# Schematic.net
KiCad netlist of a schematic drawn in Altium Designer
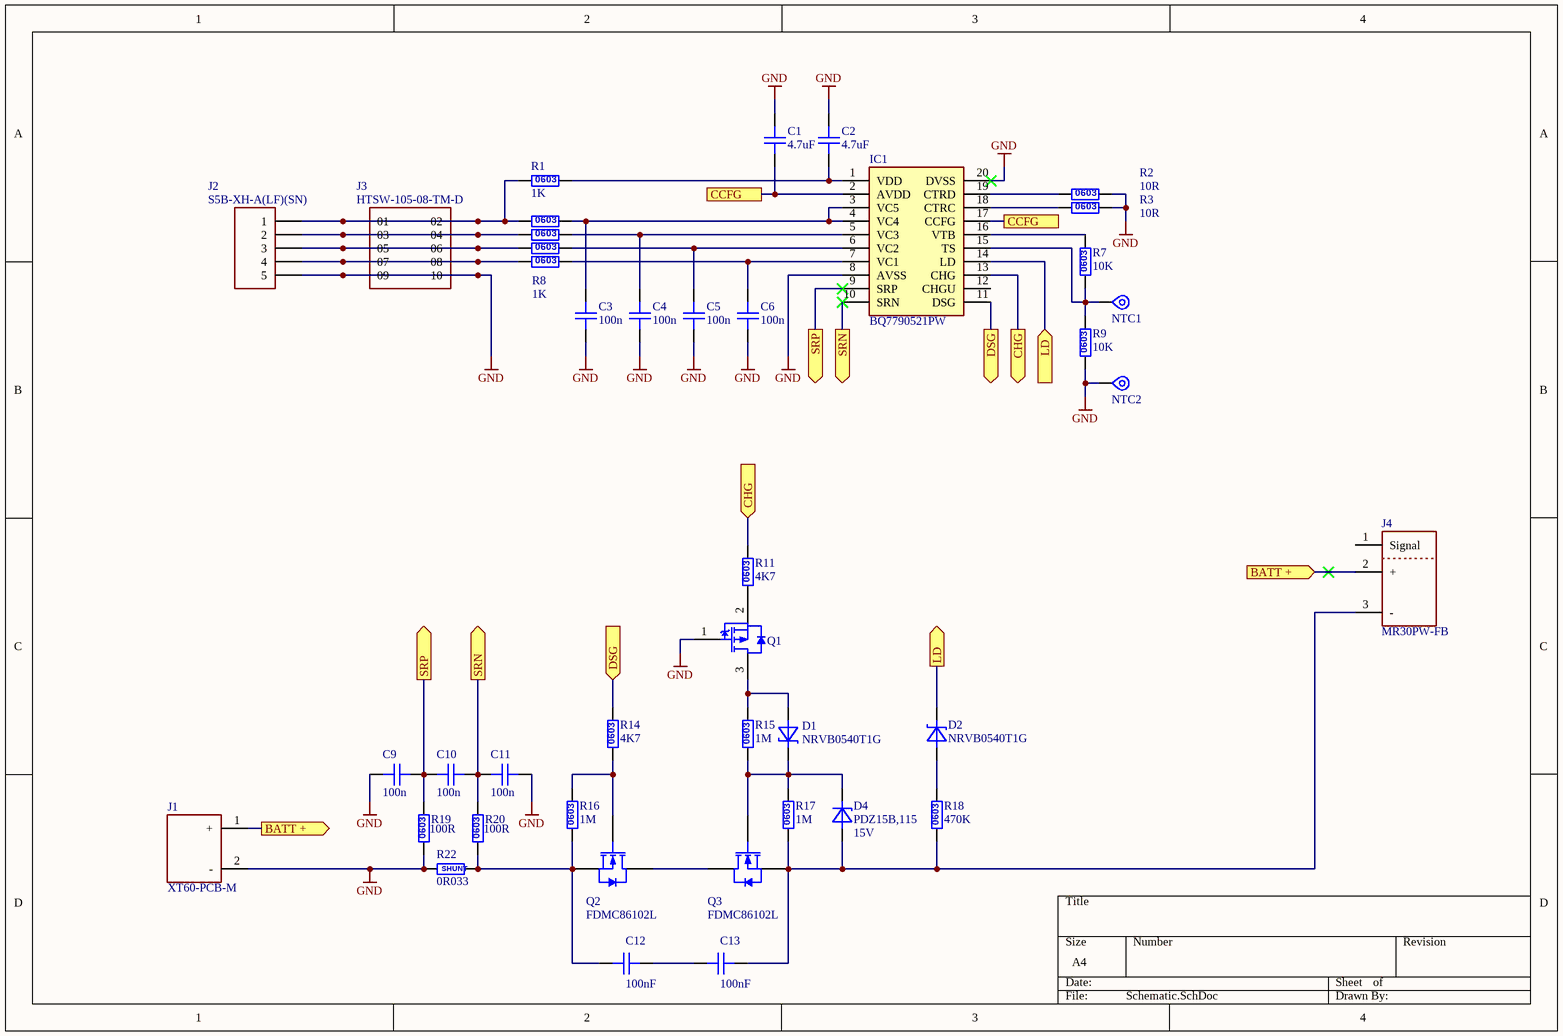
[diagram p0: Schematic.SchDoc]

(export (version "E")
  (design (tool "Eeschema 10.0.6"))
  (components
    (comp (ref "C1")
      (value "4.7uF")
      (footprint "C3216_Commercial")
      (description "Capacitor X7S")
      (fields (field (name "Comment") "GRM31CC72A475ME11L"))
      (libsource (lib "CapRes") (part "CC_1206_X7S_475"))
    )
    (comp (ref "C2")
      (value "4.7uF")
      (footprint "C3216_Commercial")
      (description "Capacitor X7S")
      (fields (field (name "Comment") "GRM31CC72A475ME11L"))
      (libsource (lib "CapRes") (part "CC_1206_X7S_475"))
    )
    (comp (ref "C3")
      (value "100n")
      (footprint "C0603")
      (description "Ceramic Capacitor X7R 50V")
      (fields (field (name "PART NUMBER") "100n/50V X7R C0603") (field (name "Comment") "06035C104K4Z2A"))
      (libsource (lib "CapRes") (part "CC_0603_X7R_104"))
    )
    (comp (ref "C4")
      (value "100n")
      (footprint "C0603")
      (description "Ceramic Capacitor X7R 50V")
      (fields (field (name "PART NUMBER") "100n/50V X7R C0603") (field (name "Comment") "06035C104K4Z2A"))
      (libsource (lib "CapRes") (part "CC_0603_X7R_104"))
    )
    (comp (ref "C5")
      (value "100n")
      (footprint "C0603")
      (description "Ceramic Capacitor X7R 50V")
      (fields (field (name "PART NUMBER") "100n/50V X7R C0603") (field (name "Comment") "06035C104K4Z2A"))
      (libsource (lib "CapRes") (part "CC_0603_X7R_104"))
    )
    (comp (ref "C6")
      (value "100n")
      (footprint "C0603")
      (description "Ceramic Capacitor X7R 50V")
      (fields (field (name "PART NUMBER") "100n/50V X7R C0603") (field (name "Comment") "06035C104K4Z2A"))
      (libsource (lib "CapRes") (part "CC_0603_X7R_104"))
    )
    (comp (ref "C9")
      (value "100n")
      (footprint "C0603")
      (description "Ceramic Capacitor X7R 50V")
      (fields (field (name "PART NUMBER") "100n/50V X7R C0603") (field (name "Comment") "06035C104K4Z2A"))
      (libsource (lib "CapRes") (part "CC_0603_X7R_104"))
    )
    (comp (ref "C10")
      (value "100n")
      (footprint "C0603")
      (description "Ceramic Capacitor X7R 50V")
      (fields (field (name "PART NUMBER") "100n/50V X7R C0603") (field (name "Comment") "06035C104K4Z2A"))
      (libsource (lib "CapRes") (part "CC_0603_X7R_104"))
    )
    (comp (ref "C11")
      (value "100n")
      (footprint "C0603")
      (description "Ceramic Capacitor X7R 50V")
      (fields (field (name "PART NUMBER") "100n/50V X7R C0603") (field (name "Comment") "06035C104K4Z2A"))
      (libsource (lib "CapRes") (part "CC_0603_X7R_104"))
    )
    (comp (ref "C12")
      (value "100nF")
      (footprint "C3216_Commercial")
      (description "Capacitor NP0")
      (fields (field (name "Comment") "GRT31C5C2A104JA12L"))
      (libsource (lib "CapRes") (part "CC_1206_NP0_104"))
    )
    (comp (ref "C13")
      (value "100nF")
      (footprint "C3216_Commercial")
      (description "Capacitor NP0")
      (fields (field (name "Comment") "GRT31C5C2A104JA12L"))
      (libsource (lib "CapRes") (part "CC_1206_NP0_104"))
    )
    (comp (ref "D1")
      (value "NRVB0540T1G")
      (footprint "SOD323")
      (description "Schottky Diode 40V, 500mA")
      (libsource (lib "Semi") (part "NRVB0540T1G"))
    )
    (comp (ref "D2")
      (value "NRVB0540T1G")
      (footprint "SOD323")
      (description "Schottky Diode 40V, 500mA")
      (libsource (lib "Semi") (part "NRVB0540T1G"))
    )
    (comp (ref "D4")
      (value "PDZ15B,115")
      (footprint "SOD323")
      (description "Zener Diode 15V, 400mW")
      (fields (field (name "ALTIUM_VALUE") "15V"))
      (libsource (lib "Semi") (part "PDZ15B,115"))
    )
    (comp (ref "IC1")
      (value "BQ7790521PW")
      (footprint "SOP65P640X120-20N")
      (description "3- to 5-series Li-Ion stackable battery protector")
      (fields (field (name "MOUSER PART NUMBER") "595-BQ7790521PW"))
      (libsource (lib "Semi") (part "BQ7790521PW"))
    )
    (comp (ref "J1")
      (value "XT60-PCB-M")
      (footprint "XT60-PCB-M")
      (description "XT60 Connector")
      (fields (field (name "MANUFACTURER_PART_NUMBER") "XT30PB"))
      (libsource (lib "CapRes") (part "XT60-PCB-M"))
    )
    (comp (ref "J2")
      (value "S5B-XH-A(LF)(SN)")
      (footprint "JST_S5B-XH-A(LF)(SN)")
      (description "Connector Header Through Hole, Right Angle 5 position 0.098 _2.50mm_")
      (fields (field (name "MF") "JST Sales") (field (name "MP") "S5B-XH-A_LF__SN_"))
      (libsource (lib "CapRes") (part "S5B-XH-A(LF)(SN)"))
    )
    (comp (ref "J3")
      (value "HTSW-105-08-TM-D")
      (footprint "SAMTEC_HTSW-105-08-TM-D")
      (fields (field (name "MP") "HTSW10508TMD") (field (name "MF") "Samtec"))
      (libsource (lib "CapRes") (part "HTSW-105-08-TM-D"))
    )
    (comp (ref "J4")
      (value "MR30PW-FB")
      (footprint "MR30PW-FB")
      (description "Connector")
      (libsource (lib "CapRes") (part "MR30PW-FB"))
    )
    (comp (ref "NTC1")
      (value "TP")
      (footprint "Pad0.8mm MPoint big")
      (description "Test Point")
      (libsource (lib "CapRes") (part "TP_PCB"))
    )
    (comp (ref "NTC2")
      (value "TP")
      (footprint "Pad0.8mm MPoint big")
      (description "Test Point")
      (libsource (lib "CapRes") (part "TP_PCB"))
    )
    (comp (ref "Q1")
      (value "FDV304P")
      (footprint "FAIR-SOT23-3_V")
      (fields (field (name "MANUFACTURER") "ON Semiconductor / Fairchild"))
      (libsource (lib "Semi") (part "FDV304P"))
    )
    (comp (ref "Q2")
      (value "FDMC86102L")
      (footprint "PowerPak1212_LFPAK33")
      (description "N-MOS 100V, 18A, 23mOhm")
      (fields (field (name "MANUFACTURER") "ON Semiconductor / Fairchild"))
      (libsource (lib "Semi") (part "FDMC86102L"))
    )
    (comp (ref "Q3")
      (value "FDMC86102L")
      (footprint "PowerPak1212_LFPAK33")
      (description "N-MOS 100V, 18A, 23mOhm")
      (fields (field (name "MANUFACTURER") "ON Semiconductor / Fairchild"))
      (libsource (lib "Semi") (part "FDMC86102L"))
    )
    (comp (ref "R1")
      (value "1K")
      (footprint "R0603")
      (description "Resistor 1%, 0.1W, 75V")
      (fields (field (name "Comment") "ERJ-3EKF1002V"))
      (libsource (lib "CapRes") (part "CR_0603_102"))
    )
    (comp (ref "R2")
      (value "10R")
      (footprint "R0603")
      (description "Resistor 1%, 0.1W, 75V")
      (fields (field (name "Comment") "CR0603-FX-10R0ELF"))
      (libsource (lib "CapRes") (part "CR_0603_100"))
    )
    (comp (ref "R3")
      (value "10R")
      (footprint "R0603")
      (description "Resistor 1%, 0.1W, 75V")
      (fields (field (name "Comment") "CR0603-FX-10R0ELF"))
      (libsource (lib "CapRes") (part "CR_0603_100"))
    )
    (comp (ref "R4")
      (value "ERJ-3EKF1002V")
      (footprint "R0603")
      (description "Resistor 1%, 0.1W, 75V")
      (libsource (lib "CapRes") (part "CR_0603_102"))
    )
    (comp (ref "R5")
      (value "ERJ-3EKF1002V")
      (footprint "R0603")
      (description "Resistor 1%, 0.1W, 75V")
      (libsource (lib "CapRes") (part "CR_0603_102"))
    )
    (comp (ref "R6")
      (value "ERJ-3EKF1002V")
      (footprint "R0603")
      (description "Resistor 1%, 0.1W, 75V")
      (libsource (lib "CapRes") (part "CR_0603_102"))
    )
    (comp (ref "R7")
      (value "10K")
      (footprint "R0603")
      (description "Resistor 1%, 0.1W, 75V")
      (fields (field (name "Comment") "CRGP0603F10K"))
      (libsource (lib "CapRes") (part "CR_0603_103"))
    )
    (comp (ref "R8")
      (value "1K")
      (footprint "R0603")
      (description "Resistor 1%, 0.1W, 75V")
      (fields (field (name "Comment") "ERJ-3EKF1002V"))
      (libsource (lib "CapRes") (part "CR_0603_102"))
    )
    (comp (ref "R9")
      (value "10K")
      (footprint "R0603")
      (description "Resistor 1%, 0.1W, 75V")
      (fields (field (name "Comment") "CRGP0603F10K"))
      (libsource (lib "CapRes") (part "CR_0603_103"))
    )
    (comp (ref "R11")
      (value "4K7")
      (footprint "R0603")
      (description "Resistor 1%, 0.1W, 75V")
      (fields (field (name "Comment") "RC0603FR-074K7L"))
      (libsource (lib "CapRes") (part "CR_0603_472"))
    )
    (comp (ref "R14")
      (value "4K7")
      (footprint "R0603")
      (description "Resistor 1%, 0.1W, 75V")
      (fields (field (name "Comment") "RC0603FR-074K7L"))
      (libsource (lib "CapRes") (part "CR_0603_472"))
    )
    (comp (ref "R15")
      (value "1M")
      (footprint "R0603")
      (description "Resistor 1%, 0.1W, 75V")
      (fields (field (name "PART NUMBER") "1M0 R0603") (field (name "Comment") "RC0603JR-071ML"))
      (libsource (lib "CapRes") (part "CR_0603_105"))
    )
    (comp (ref "R16")
      (value "1M")
      (footprint "R0603")
      (description "Resistor 1%, 0.1W, 75V")
      (fields (field (name "PART NUMBER") "1M0 R0603") (field (name "Comment") "RC0603JR-071ML"))
      (libsource (lib "CapRes") (part "CR_0603_105"))
    )
    (comp (ref "R17")
      (value "1M")
      (footprint "R0603")
      (description "Resistor 1%, 0.1W, 75V")
      (fields (field (name "PART NUMBER") "1M0 R0603") (field (name "Comment") "RC0603JR-071ML"))
      (libsource (lib "CapRes") (part "CR_0603_105"))
    )
    (comp (ref "R18")
      (value "470K")
      (footprint "R0603")
      (description "Resistor 1%, 0.1W, 75V")
      (fields (field (name "Comment") "CRGCQ0603F470K"))
      (libsource (lib "CapRes") (part "CR_0603_474"))
    )
    (comp (ref "R19")
      (value "100R")
      (footprint "R0603")
      (description "Resistor 1%, 0.1W, 75V")
      (fields (field (name "Comment") "RC0603FR-07100RL"))
      (libsource (lib "CapRes") (part "CR_0603_101"))
    )
    (comp (ref "R20")
      (value "100R")
      (footprint "R0603")
      (description "Resistor 1%, 0.1W, 75V")
      (fields (field (name "Comment") "RC0603FR-07100RL"))
      (libsource (lib "CapRes") (part "CR_0603_101"))
    )
    (comp (ref "R22")
      (value "0R033")
      (footprint "Shunt_2512")
      (description "Current Sense Resistor 1%, 3W, AEC-Q200")
      (fields (field (name "Comment") "GMR100HTBFMR033"))
      (libsource (lib "CapRes") (part "SHUNT_2512_0R033"))
    )
  )
  (nets
    (net (code "1") (name "/BATT +") (class "Default")
      (node (ref "J1") (pin "1") (pinfunction "+_1") (pintype "passive"))
      (node (ref "J4") (pin "2") (pinfunction "+_2") (pintype "passive"))
    )
    (net (code "2") (name "/CCFG") (class "Default")
      (node (ref "C1") (pin "1") (pinfunction "1_1") (pintype "passive"))
      (node (ref "IC1") (pin "17") (pinfunction "CCFG_17") (pintype "passive"))
      (node (ref "IC1") (pin "2") (pinfunction "AVDD_2") (pintype "passive"))
    )
    (net (code "3") (name "/CHG") (class "Default")
      (node (ref "IC1") (pin "13") (pinfunction "CHG_13") (pintype "passive"))
      (node (ref "R11") (pin "1") (pinfunction "1_1") (pintype "passive"))
    )
    (net (code "4") (name "/DSG") (class "Default")
      (node (ref "IC1") (pin "11") (pinfunction "DSG_11") (pintype "passive"))
      (node (ref "R14") (pin "1") (pinfunction "1_1") (pintype "passive"))
    )
    (net (code "5") (name "/LD") (class "Default")
      (node (ref "D2") (pin "2") (pinfunction "C_2") (pintype "passive"))
      (node (ref "IC1") (pin "14") (pinfunction "LD_14") (pintype "passive"))
    )
    (net (code "6") (name "/SRN") (class "Default")
      (node (ref "C10") (pin "2") (pinfunction "2_2") (pintype "passive"))
      (node (ref "C11") (pin "1") (pinfunction "1_1") (pintype "passive"))
      (node (ref "IC1") (pin "10") (pinfunction "SRN_10") (pintype "passive"))
      (node (ref "R20") (pin "1") (pinfunction "1_1") (pintype "passive"))
    )
    (net (code "7") (name "/SRP") (class "Default")
      (node (ref "C10") (pin "1") (pinfunction "1_1") (pintype "passive"))
      (node (ref "C9") (pin "2") (pinfunction "2_2") (pintype "passive"))
      (node (ref "IC1") (pin "9") (pinfunction "SRP_9") (pintype "passive"))
      (node (ref "R19") (pin "1") (pinfunction "1_1") (pintype "passive"))
    )
    (net (code "8") (name "GND") (class "Default")
      (node (ref "C1") (pin "2") (pinfunction "2_2") (pintype "passive"))
      (node (ref "C11") (pin "2") (pinfunction "2_2") (pintype "passive"))
      (node (ref "C2") (pin "2") (pinfunction "2_2") (pintype "passive"))
      (node (ref "C3") (pin "1") (pinfunction "1_1") (pintype "passive"))
      (node (ref "C4") (pin "1") (pinfunction "1_1") (pintype "passive"))
      (node (ref "C5") (pin "1") (pinfunction "1_1") (pintype "passive"))
      (node (ref "C6") (pin "1") (pinfunction "1_1") (pintype "passive"))
      (node (ref "C9") (pin "1") (pinfunction "1_1") (pintype "passive"))
      (node (ref "IC1") (pin "20") (pinfunction "DVSS_20") (pintype "passive"))
      (node (ref "IC1") (pin "8") (pinfunction "AVSS_8") (pintype "passive"))
      (node (ref "J1") (pin "2") (pinfunction "-_2") (pintype "passive"))
      (node (ref "J2") (pin "5") (pinfunction "5_5") (pintype "passive"))
      (node (ref "J3") (pin "09") (pinfunction "09_09") (pintype "passive"))
      (node (ref "J3") (pin "10") (pinfunction "10_10") (pintype "passive"))
      (node (ref "NTC2") (pin "1") (pinfunction "1_1") (pintype "passive"))
      (node (ref "Q1") (pin "1") (pinfunction "G_1") (pintype "passive"))
      (node (ref "R19") (pin "2") (pinfunction "2_2") (pintype "passive"))
      (node (ref "R2") (pin "1") (pinfunction "1_1") (pintype "passive"))
      (node (ref "R22") (pin "1") (pinfunction "1_1") (pintype "passive"))
      (node (ref "R3") (pin "1") (pinfunction "1_1") (pintype "passive"))
      (node (ref "R9") (pin "2") (pinfunction "2_2") (pintype "passive"))
    )
    (net (code "9") (name "Net-(C12-Pad1)") (class "Default")
      (node (ref "C12") (pin "1") (pinfunction "1_1") (pintype "passive"))
      (node (ref "Q2") (pin "1") (pinfunction "SOURCE_1") (pintype "passive"))
      (node (ref "Q2") (pin "2") (pinfunction "SOURCE_2") (pintype "passive"))
      (node (ref "Q2") (pin "3") (pinfunction "SOURCE_3") (pintype "passive"))
      (node (ref "R16") (pin "2") (pinfunction "2_2") (pintype "passive"))
      (node (ref "R20") (pin "2") (pinfunction "2_2") (pintype "passive"))
      (node (ref "R22") (pin "2") (pinfunction "2_2") (pintype "passive"))
    )
    (net (code "10") (name "Net-(C12-Pad2)") (class "Default")
      (node (ref "C12") (pin "2") (pinfunction "2_2") (pintype "passive"))
      (node (ref "C13") (pin "1") (pinfunction "1_1") (pintype "passive"))
    )
    (net (code "11") (name "Net-(D1-A)") (class "Default")
      (node (ref "D1") (pin "1") (pinfunction "A_1") (pintype "passive"))
      (node (ref "Q1") (pin "3") (pinfunction "D_3") (pintype "passive"))
      (node (ref "R15") (pin "1") (pinfunction "1_1") (pintype "passive"))
    )
    (net (code "12") (name "Net-(D1-C)") (class "Default")
      (node (ref "D1") (pin "2") (pinfunction "C_2") (pintype "passive"))
      (node (ref "D4") (pin "2") (pinfunction "C_2") (pintype "passive"))
      (node (ref "Q3") (pin "4") (pinfunction "GATE_4") (pintype "passive"))
      (node (ref "R15") (pin "2") (pinfunction "2_2") (pintype "passive"))
      (node (ref "R17") (pin "1") (pinfunction "1_1") (pintype "passive"))
    )
    (net (code "13") (name "Net-(D2-A)") (class "Default")
      (node (ref "D2") (pin "1") (pinfunction "A_1") (pintype "passive"))
      (node (ref "R18") (pin "1") (pinfunction "1_1") (pintype "passive"))
    )
    (net (code "14") (name "Net-(D4-A)") (class "Default")
      (node (ref "C13") (pin "2") (pinfunction "2_2") (pintype "passive"))
      (node (ref "D4") (pin "1") (pinfunction "A_1") (pintype "passive"))
      (node (ref "J4") (pin "3") (pinfunction "-_3") (pintype "passive"))
      (node (ref "Q3") (pin "1") (pinfunction "SOURCE_1") (pintype "passive"))
      (node (ref "Q3") (pin "2") (pinfunction "SOURCE_2") (pintype "passive"))
      (node (ref "Q3") (pin "3") (pinfunction "SOURCE_3") (pintype "passive"))
      (node (ref "R17") (pin "2") (pinfunction "2_2") (pintype "passive"))
      (node (ref "R18") (pin "2") (pinfunction "2_2") (pintype "passive"))
    )
    (net (code "15") (name "Net-(IC1-CTRC)") (class "Default")
      (node (ref "IC1") (pin "18") (pinfunction "CTRC_18") (pintype "passive"))
      (node (ref "R3") (pin "2") (pinfunction "2_2") (pintype "passive"))
    )
    (net (code "16") (name "Net-(IC1-CTRD)") (class "Default")
      (node (ref "IC1") (pin "19") (pinfunction "CTRD_19") (pintype "passive"))
      (node (ref "R2") (pin "2") (pinfunction "2_2") (pintype "passive"))
    )
    (net (code "17") (name "Net-(IC1-TS)") (class "Default")
      (node (ref "IC1") (pin "15") (pinfunction "TS_15") (pintype "passive"))
      (node (ref "NTC1") (pin "1") (pinfunction "1_1") (pintype "passive"))
      (node (ref "R7") (pin "2") (pinfunction "2_2") (pintype "passive"))
      (node (ref "R9") (pin "1") (pinfunction "1_1") (pintype "passive"))
    )
    (net (code "18") (name "Net-(IC1-VC1)") (class "Default")
      (node (ref "C6") (pin "2") (pinfunction "2_2") (pintype "passive"))
      (node (ref "IC1") (pin "7") (pinfunction "VC1_7") (pintype "passive"))
      (node (ref "R6") (pin "1") (pinfunction "1_1") (pintype "passive"))
    )
    (net (code "19") (name "Net-(IC1-VC2)") (class "Default")
      (node (ref "C5") (pin "2") (pinfunction "2_2") (pintype "passive"))
      (node (ref "IC1") (pin "6") (pinfunction "VC2_6") (pintype "passive"))
      (node (ref "R5") (pin "1") (pinfunction "1_1") (pintype "passive"))
    )
    (net (code "20") (name "Net-(IC1-VC3)") (class "Default")
      (node (ref "C4") (pin "2") (pinfunction "2_2") (pintype "passive"))
      (node (ref "IC1") (pin "5") (pinfunction "VC3_5") (pintype "passive"))
      (node (ref "R4") (pin "1") (pinfunction "1_1") (pintype "passive"))
    )
    (net (code "21") (name "Net-(IC1-VC4)") (class "Default")
      (node (ref "C3") (pin "2") (pinfunction "2_2") (pintype "passive"))
      (node (ref "IC1") (pin "3") (pinfunction "VC5_3") (pintype "passive"))
      (node (ref "IC1") (pin "4") (pinfunction "VC4_4") (pintype "passive"))
      (node (ref "R8") (pin "1") (pinfunction "1_1") (pintype "passive"))
    )
    (net (code "22") (name "Net-(IC1-VDD)") (class "Default")
      (node (ref "C2") (pin "1") (pinfunction "1_1") (pintype "passive"))
      (node (ref "IC1") (pin "1") (pinfunction "VDD_1") (pintype "passive"))
      (node (ref "R1") (pin "1") (pinfunction "1_1") (pintype "passive"))
    )
    (net (code "23") (name "Net-(IC1-VTB)") (class "Default")
      (node (ref "IC1") (pin "16") (pinfunction "VTB_16") (pintype "passive"))
      (node (ref "R7") (pin "1") (pinfunction "1_1") (pintype "passive"))
    )
    (net (code "24") (name "Net-(J2-Pad1)") (class "Default")
      (node (ref "J2") (pin "1") (pinfunction "1_1") (pintype "passive"))
      (node (ref "J3") (pin "01") (pinfunction "01_01") (pintype "passive"))
      (node (ref "J3") (pin "02") (pinfunction "02_02") (pintype "passive"))
      (node (ref "R1") (pin "2") (pinfunction "2_2") (pintype "passive"))
      (node (ref "R8") (pin "2") (pinfunction "2_2") (pintype "passive"))
    )
    (net (code "25") (name "Net-(J2-Pad2)") (class "Default")
      (node (ref "J2") (pin "2") (pinfunction "2_2") (pintype "passive"))
      (node (ref "J3") (pin "03") (pinfunction "03_03") (pintype "passive"))
      (node (ref "J3") (pin "04") (pinfunction "04_04") (pintype "passive"))
      (node (ref "R4") (pin "2") (pinfunction "2_2") (pintype "passive"))
    )
    (net (code "26") (name "Net-(J2-Pad3)") (class "Default")
      (node (ref "J2") (pin "3") (pinfunction "3_3") (pintype "passive"))
      (node (ref "J3") (pin "05") (pinfunction "05_05") (pintype "passive"))
      (node (ref "J3") (pin "06") (pinfunction "06_06") (pintype "passive"))
      (node (ref "R5") (pin "2") (pinfunction "2_2") (pintype "passive"))
    )
    (net (code "27") (name "Net-(J2-Pad4)") (class "Default")
      (node (ref "J2") (pin "4") (pinfunction "4_4") (pintype "passive"))
      (node (ref "J3") (pin "07") (pinfunction "07_07") (pintype "passive"))
      (node (ref "J3") (pin "08") (pinfunction "08_08") (pintype "passive"))
      (node (ref "R6") (pin "2") (pinfunction "2_2") (pintype "passive"))
    )
    (net (code "28") (name "Net-(Q1-S)") (class "Default")
      (node (ref "Q1") (pin "2") (pinfunction "S_2") (pintype "passive"))
      (node (ref "R11") (pin "2") (pinfunction "2_2") (pintype "passive"))
    )
    (net (code "29") (name "Net-(Q2-DRAIN)") (class "Default")
      (node (ref "Q2") (pin "5") (pinfunction "DRAIN_5") (pintype "passive"))
      (node (ref "Q3") (pin "5") (pinfunction "DRAIN_5") (pintype "passive"))
    )
    (net (code "30") (name "Net-(Q2-GATE)") (class "Default")
      (node (ref "Q2") (pin "4") (pinfunction "GATE_4") (pintype "passive"))
      (node (ref "R14") (pin "2") (pinfunction "2_2") (pintype "passive"))
      (node (ref "R16") (pin "1") (pinfunction "1_1") (pintype "passive"))
    )
    (net (code "31") (name "unconnected-(IC1-CHGU-Pad12)") (class "Default")
      (node (ref "IC1") (pin "12") (pinfunction "CHGU_12") (pintype "passive"))
    )
    (net (code "32") (name "unconnected-(J4-Signal-Pad1)") (class "Default")
      (node (ref "J4") (pin "1") (pinfunction "Signal_1") (pintype "passive"))
    )
  )
)
